# 01-_Power_Regulators.net
KiCad netlist of a schematic drawn in Altium Designer
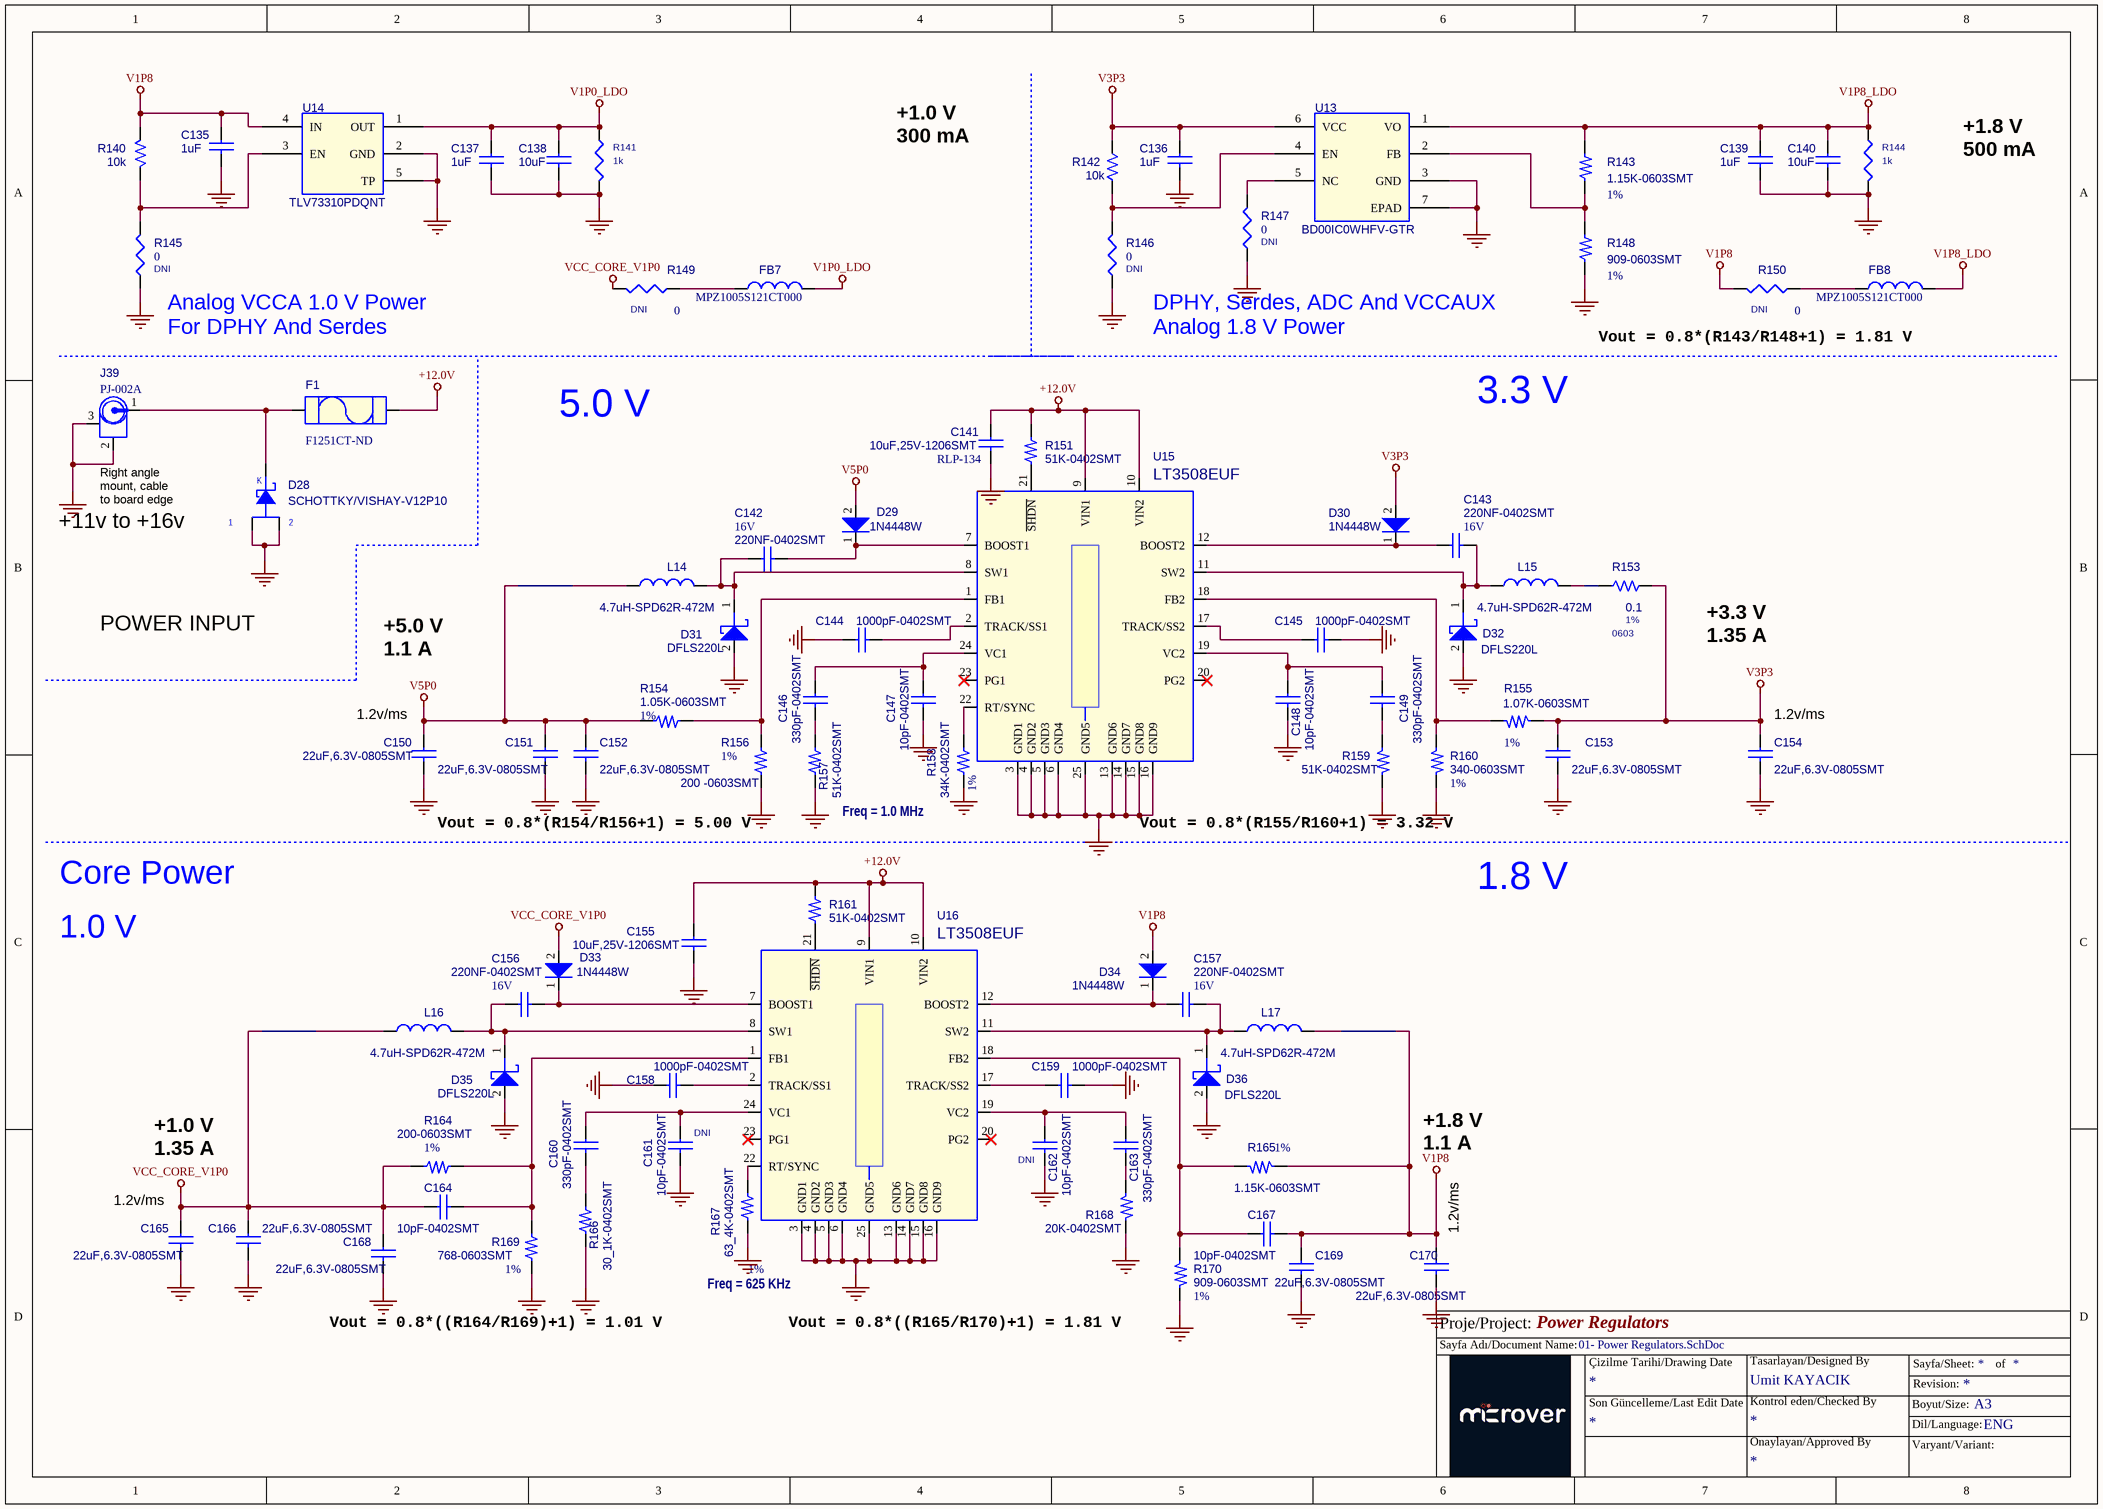
[diagram p0: 01- Power Regulators.SchDoc]

(export (version "E")
  (design (tool "Eeschema 10.0.6"))
  (components
    (comp (ref "C135")
      (value "1uF")
      (footprint "C0603")
      (description "CAP CER 10UF 10V 20% X6S 0603")
      (fields
        (field (name "MANUFACTURER PART NUMBER") "CL10X106MP8NRNC")
        (field (name "MANUFACTURER") "Samsung")
      )
      (libsource (lib "*") (part "CAP NP"))
    )
    (comp (ref "C136")
      (value "1uF")
      (footprint "C0603")
      (description "CAP CER 10UF 10V 20% X6S 0603")
      (fields
        (field (name "MANUFACTURER PART NUMBER") "CL10X106MP8NRNC")
        (field (name "MANUFACTURER") "Samsung")
      )
      (libsource (lib "*") (part "CAP NP"))
    )
    (comp (ref "C137")
      (value "1uF")
      (footprint "C0603")
      (description "CAP CER 10UF 10V 20% X6S 0603")
      (fields
        (field (name "MANUFACTURER PART NUMBER") "CL10X106MP8NRNC")
        (field (name "MANUFACTURER") "Samsung")
      )
      (libsource (lib "*") (part "CAP NP"))
    )
    (comp (ref "C138")
      (value "10uF")
      (footprint "C0603")
      (description "CAP CER 10UF 10V 20% X6S 0603")
      (fields (field (name "MFG") "Samsung") (field (name "MAN. PART #") "CL10X106MP8NRNC"))
      (libsource (lib "*") (part "CAP NP"))
    )
    (comp (ref "C139")
      (value "1uF")
      (footprint "C0603")
      (description "CAP CER 10UF 10V 20% X6S 0603")
      (fields (field (name "MFG") "Samsung") (field (name "MAN. PART #") "CL10X106MP8NRNC"))
      (libsource (lib "*") (part "CAP NP"))
    )
    (comp (ref "C140")
      (value "10uF")
      (footprint "C0603")
      (description "CAP CER 10UF 10V 20% X6S 0603")
      (fields (field (name "MFG") "Samsung") (field (name "MAN. PART #") "CL10X106MP8NRNC"))
      (libsource (lib "*") (part "CAP NP"))
    )
    (comp (ref "C141")
      (value "10uF,25V-1206SMT")
      (footprint "RLP-134")
      (fields (field (name "PCB FOOTPRINT") "RLP-134"))
      (libsource (lib "*") (part "CAP-NP"))
    )
    (comp (ref "C142")
      (value "220NF-0402SMT")
      (footprint "RLP-130-A")
      (fields (field (name "COMPFIXED") "16V"))
      (libsource (lib "*") (part "CAP-NP"))
    )
    (comp (ref "C143")
      (value "220NF-0402SMT")
      (footprint "RLP-130-A")
      (fields (field (name "COMPFIXED") "16V"))
      (libsource (lib "*") (part "CAP-NP"))
    )
    (comp (ref "C144") (value "1000pF-0402SMT") (footprint "RLP-130-A") (libsource (lib "*") (part "CAP-NP")))
    (comp (ref "C145") (value "1000pF-0402SMT") (footprint "RLP-130-A") (libsource (lib "*") (part "CAP-NP")))
    (comp (ref "C146") (value "330pF-0402SMT") (footprint "RLP-130-A") (libsource (lib "*") (part "CAP-NP")))
    (comp (ref "C147") (value "10pF-0402SMT") (footprint "RLP-130-A") (libsource (lib "*") (part "CAP-NP")))
    (comp (ref "C148") (value "10pF-0402SMT") (footprint "RLP-130-A") (libsource (lib "*") (part "CAP-NP")))
    (comp (ref "C149") (value "330pF-0402SMT") (footprint "RLP-130-A") (libsource (lib "*") (part "CAP-NP")))
    (comp (ref "C150")
      (value "22uF,6.3V-0805SMT")
      (footprint "RLP-133")
      (description "CAP CER 22UF 10V X5R 0805")
      (fields
        (field (name "MANUFACTURER") "Samsung")
        (field (name "MANUFACTURER PART NUMBER") "CL21A226KPCLRNC")
      )
      (libsource (lib "*") (part "CAP-NP"))
    )
    (comp (ref "C151")
      (value "22uF,6.3V-0805SMT")
      (footprint "RLP-133")
      (description "CAP CER 22UF 10V X5R 0805")
      (fields
        (field (name "MANUFACTURER") "Samsung")
        (field (name "MANUFACTURER PART NUMBER") "CL21A226KPCLRNC")
      )
      (libsource (lib "*") (part "CAP-NP"))
    )
    (comp (ref "C152")
      (value "22uF,6.3V-0805SMT")
      (footprint "RLP-133")
      (description "CAP CER 22UF 10V X5R 0805")
      (fields
        (field (name "MANUFACTURER") "Samsung")
        (field (name "MANUFACTURER PART NUMBER") "CL21A226KPCLRNC")
      )
      (libsource (lib "*") (part "CAP-NP"))
    )
    (comp (ref "C153")
      (value "22uF,6.3V-0805SMT")
      (footprint "RLP-133")
      (description "CAP CER 22UF 10V X5R 0805")
      (fields
        (field (name "MANUFACTURER PART NUMBER") "CL21A226KPCLRNC")
        (field (name "MANUFACTURER") "Samsung")
      )
      (libsource (lib "*") (part "CAP-NP"))
    )
    (comp (ref "C154")
      (value "22uF,6.3V-0805SMT")
      (footprint "RLP-133")
      (description "CAP CER 22UF 10V X5R 0805")
      (fields
        (field (name "MANUFACTURER PART NUMBER") "CL21A226KPCLRNC")
        (field (name "MANUFACTURER") "Samsung")
      )
      (libsource (lib "*") (part "CAP-NP"))
    )
    (comp (ref "C155") (value "10uF,25V-1206SMT") (footprint "RLP-134") (libsource (lib "*") (part "CAP-NP")))
    (comp (ref "C156")
      (value "220NF-0402SMT")
      (footprint "RLP-130-A")
      (fields (field (name "COMPFIXED") "16V"))
      (libsource (lib "*") (part "CAP-NP"))
    )
    (comp (ref "C157")
      (value "220NF-0402SMT")
      (footprint "RLP-130-A")
      (fields (field (name "COMPFIXED") "16V"))
      (libsource (lib "*") (part "CAP-NP"))
    )
    (comp (ref "C158") (value "1000pF-0402SMT") (footprint "RLP-130-A") (libsource (lib "*") (part "CAP-NP")))
    (comp (ref "C159") (value "1000pF-0402SMT") (footprint "RLP-130-A") (libsource (lib "*") (part "CAP-NP")))
    (comp (ref "C160") (value "330pF-0402SMT") (footprint "RLP-130-A") (libsource (lib "*") (part "CAP-NP")))
    (comp (ref "C161")
      (value "10pF-0402SMT")
      (footprint "RLP-130-A")
      (fields (field (name "POPULATE") "DNI"))
      (libsource (lib "*") (part "CAP-NP"))
    )
    (comp (ref "C162")
      (value "10pF-0402SMT")
      (footprint "RLP-130-A")
      (fields (field (name "POPULATE") "DNI"))
      (libsource (lib "*") (part "CAP-NP"))
    )
    (comp (ref "C163") (value "330pF-0402SMT") (footprint "RLP-130-A") (libsource (lib "*") (part "CAP-NP")))
    (comp (ref "C164") (value "10pF-0402SMT") (footprint "RLP-130-A") (libsource (lib "*") (part "CAP-NP")))
    (comp (ref "C165")
      (value "22uF,6.3V-0805SMT")
      (footprint "RLP-133")
      (description "CAP CER 22UF 10V X5R 0805")
      (fields
        (field (name "MANUFACTURER PART NUMBER") "CL21A226KPCLRNC")
        (field (name "MANUFACTURER") "Samsung")
      )
      (libsource (lib "*") (part "CAP-NP"))
    )
    (comp (ref "C166")
      (value "22uF,6.3V-0805SMT")
      (footprint "RLP-133")
      (description "CAP CER 22UF 10V X5R 0805")
      (fields
        (field (name "MANUFACTURER") "Samsung")
        (field (name "MANUFACTURER PART NUMBER") "CL21A226KPCLRNC")
      )
      (libsource (lib "*") (part "CAP-NP"))
    )
    (comp (ref "C167") (value "10pF-0402SMT") (footprint "RLP-130-A") (libsource (lib "*") (part "CAP-NP")))
    (comp (ref "C168")
      (value "22uF,6.3V-0805SMT")
      (footprint "RLP-133")
      (description "CAP CER 22UF 10V X5R 0805")
      (fields
        (field (name "MANUFACTURER") "Samsung")
        (field (name "MANUFACTURER PART NUMBER") "CL21A226KPCLRNC")
      )
      (libsource (lib "*") (part "CAP-NP"))
    )
    (comp (ref "C169")
      (value "22uF,6.3V-0805SMT")
      (footprint "RLP-133")
      (description "CAP CER 22UF 10V X5R 0805")
      (fields
        (field (name "MANUFACTURER PART NUMBER") "CL21A226KPCLRNC")
        (field (name "MANUFACTURER") "Samsung")
      )
      (libsource (lib "*") (part "CAP-NP"))
    )
    (comp (ref "C170")
      (value "22uF,6.3V-0805SMT")
      (footprint "RLP-133")
      (description "CAP CER 22UF 10V X5R 0805")
      (fields
        (field (name "MANUFACTURER") "Samsung")
        (field (name "MANUFACTURER PART NUMBER") "CL21A226KPCLRNC")
      )
      (libsource (lib "*") (part "CAP-NP"))
    )
    (comp (ref "D28")
      (value "SCHOTTKY/VISHAY-V12P10")
      (footprint "V12P10")
      (libsource (lib "*") (part "DIODE SCHOTTKY21"))
    )
    (comp (ref "D29") (value "1N4448W") (footprint "1N4448W") (libsource (lib "*") (part "DIODE_0")))
    (comp (ref "D30") (value "1N4448W") (footprint "1N4448W") (libsource (lib "*") (part "DIODE_0")))
    (comp (ref "D31") (value "DFLS220L") (footprint "DFLS220L") (libsource (lib "*") (part "D-SCHOTTKY_0")))
    (comp (ref "D32") (value "DFLS220L") (footprint "DFLS220L") (libsource (lib "*") (part "D-SCHOTTKY_0")))
    (comp (ref "D33") (value "1N4448W") (footprint "1N4448W") (libsource (lib "*") (part "DIODE_0")))
    (comp (ref "D34") (value "1N4448W") (footprint "1N4448W") (libsource (lib "*") (part "DIODE_0")))
    (comp (ref "D35") (value "DFLS220L") (footprint "DFLS220L") (libsource (lib "*") (part "D-SCHOTTKY_0")))
    (comp (ref "D36") (value "DFLS220L") (footprint "DFLS220L") (libsource (lib "*") (part "D-SCHOTTKY_0")))
    (comp (ref "F1")
      (value "F1251CT-ND")
      (footprint "0154010")
      (description "5A Fast-Blo SMT Socketed Fuse")
      (libsource (lib "*") (part "SMTFUSE_0"))
    )
    (comp (ref "FB7")
      (value "MPZ1005S121CT000")
      (footprint "FB0402")
      (description "FERRITE BEAD 120 OHM 0402 1LN")
      (fields (field (name "MANUFACTURER") "TDK Corporation"))
      (libsource (lib "*") (part "INDUCTOR_1"))
    )
    (comp (ref "FB8")
      (value "MPZ1005S121CT000")
      (footprint "FB0402")
      (description "FERRITE BEAD 120 OHM 0402 1LN")
      (fields (field (name "MANUFACTURER") "TDK Corporation"))
      (libsource (lib "*") (part "INDUCTOR_1"))
    )
    (comp (ref "J39")
      (value "PJ-002A")
      (footprint "pj_002a_3p")
      (description "Male Power Jack 2.1mm")
      (libsource (lib "*") (part "22HP037A"))
    )
    (comp (ref "L14") (value "4.7uH-SPD62R-472M") (footprint "SPD62R") (libsource (lib "*") (part "IND")))
    (comp (ref "L15") (value "4.7uH-SPD62R-472M") (footprint "SPD62R") (libsource (lib "") (part "IND_1")))
    (comp (ref "L16") (value "4.7uH-SPD62R-472M") (footprint "SPD62R") (libsource (lib "*") (part "IND")))
    (comp (ref "L17") (value "4.7uH-SPD62R-472M") (footprint "SPD62R") (libsource (lib "") (part "IND_1")))
    (comp (ref "R140")
      (value "10k")
      (footprint "R0402")
      (description "RES SMD 4.7K OHM 5% 1/10W 0402")
      (fields (field (name "VOLTAGE") "RVMAX") (field (name "POWER") "RMAX"))
      (libsource (lib "Chronos") (part "R_Dup2"))
    )
    (comp (ref "R141")
      (value "1k")
      (footprint "R0402")
      (description "RES SMD 1K OHM 1% 1/10W 0402")
      (fields
        (field (name "MFG") "Stackpole Electronics Inc")
        (field (name "MANUFACTURER PART NUMBER") "ERJ-2RKF1001X")
      )
      (libsource (lib "*") (part "RES_1K_1W16_0402_5P"))
    )
    (comp (ref "R142")
      (value "10k")
      (footprint "R0402")
      (description "RES SMD 4.7K OHM 5% 1/10W 0402")
      (fields (field (name "VOLTAGE") "RVMAX") (field (name "POWER") "RMAX"))
      (libsource (lib "*") (part "R_Dup2"))
    )
    (comp (ref "R143")
      (value "1.15K-0603SMT")
      (footprint "RLP-101")
      (fields (field (name "COMPFIXED") "1%"))
      (libsource (lib "*") (part "R_Dup1"))
    )
    (comp (ref "R144")
      (value "1k")
      (footprint "R0402")
      (description "RES SMD 1K OHM 1% 1/10W 0402")
      (fields
        (field (name "MFG") "Stackpole Electronics Inc")
        (field (name "MANUFACTURER PART NUMBER") "ERJ-2RKF1001X")
      )
      (libsource (lib "*") (part "RES_1K_1W16_0402_5P"))
    )
    (comp (ref "R145")
      (value "0")
      (footprint "R0402")
      (description "RES 0.0 OHM 1/10W JUMP 0402 SMD")
      (fields
        (field (name "MANUFACTURER") "Yageo")
        (field (name "MANUFACTURER PART NUMBER") "RC0603JR-070RL")
        (field (name "ASSY") "DNI")
      )
      (libsource (lib "*") (part "0R_0603"))
    )
    (comp (ref "R146")
      (value "0")
      (footprint "R0603")
      (description "RES 0.0 OHM 1/10W JUMP 0603 SMD")
      (fields
        (field (name "MANUFACTURER") "Yageo")
        (field (name "MANUFACTURER PART NUMBER") "RC0603JR-070RL")
        (field (name "ASSY") "DNI")
      )
      (libsource (lib "*") (part "0R_0603"))
    )
    (comp (ref "R147")
      (value "0")
      (footprint "R0603")
      (description "RES 0.0 OHM 1/10W JUMP 0603 SMD")
      (fields
        (field (name "MANUFACTURER") "Yageo")
        (field (name "MANUFACTURER PART NUMBER") "RC0603JR-070RL")
        (field (name "ASSY") "DNI")
      )
      (libsource (lib "*") (part "0R_0603"))
    )
    (comp (ref "R148")
      (value "909-0603SMT")
      (footprint "RLP-101")
      (fields (field (name "COMPFIXED") "1%"))
      (libsource (lib "*") (part "R_Dup1"))
    )
    (comp (ref "R149")
      (value "0")
      (footprint "R0603")
      (description "RES 0.0 OHM 1/10W JUMP 0603 SMD")
      (fields
        (field (name "MANUFACTURER") "Yageo")
        (field (name "MANUFACTURER PART NUMBER") "RC0603JR-070RL")
        (field (name "ASSY") "DNI")
      )
      (libsource (lib "*") (part "0R_0603"))
    )
    (comp (ref "R150")
      (value "0")
      (footprint "R0603")
      (description "RES 0.0 OHM 1/10W JUMP 0603 SMD")
      (fields
        (field (name "MANUFACTURER") "Yageo")
        (field (name "MANUFACTURER PART NUMBER") "RC0603JR-070RL")
        (field (name "ASSY") "DNI")
      )
      (libsource (lib "*") (part "0R_0603"))
    )
    (comp (ref "R151") (value "51K-0402SMT") (footprint "RLP-100") (libsource (lib "*") (part "R_Dup1")))
    (comp (ref "R153")
      (value "0.1")
      (footprint "0603")
      (fields
        (field (name "VOLTAGE") "RVMAX")
        (field (name "POWER") "RMAX")
        (field (name "TOLLERANCE") "1%")
        (field (name "PCB FOOTPRINT") "0603")
      )
      (libsource (lib "*") (part "R_Dup2"))
    )
    (comp (ref "R154")
      (value "1.05K-0603SMT")
      (footprint "RLP-101")
      (fields (field (name "COMPFIXED") "1%"))
      (libsource (lib "*") (part "R_Dup1"))
    )
    (comp (ref "R155")
      (value "1.07K-0603SMT")
      (footprint "RLP-101")
      (fields (field (name "COMPFIXED") "1%"))
      (libsource (lib "*") (part "R_Dup1"))
    )
    (comp (ref "R156")
      (value "200 -0603SMT")
      (footprint "RLP-101")
      (fields (field (name "COMPFIXED") "1%"))
      (libsource (lib "*") (part "R_Dup1"))
    )
    (comp (ref "R157") (value "51K-0402SMT") (footprint "RLP-100") (libsource (lib "*") (part "R_Dup1")))
    (comp (ref "R158")
      (value "34K-0402SMT")
      (footprint "RLP-100")
      (fields (field (name "COMPGROUP") "Freq = 1.0 MHz") (field (name "COMPFIXED") "1%"))
      (libsource (lib "*") (part "R_Dup1"))
    )
    (comp (ref "R159") (value "51K-0402SMT") (footprint "RLP-100") (libsource (lib "*") (part "R_Dup1")))
    (comp (ref "R160")
      (value "340-0603SMT")
      (footprint "RLP-101")
      (fields (field (name "COMPFIXED") "1%"))
      (libsource (lib "*") (part "R_Dup1"))
    )
    (comp (ref "R161") (value "51K-0402SMT") (footprint "RLP-100") (libsource (lib "*") (part "R_Dup1")))
    (comp (ref "R164")
      (value "200-0603SMT")
      (footprint "RLP-101")
      (fields (field (name "COMPFIXED") "1%"))
      (libsource (lib "*") (part "R_Dup1"))
    )
    (comp (ref "R165")
      (value "1.15K-0603SMT")
      (footprint "RLP-101")
      (fields (field (name "COMPFIXED") "1%"))
      (libsource (lib "*") (part "R_Dup1"))
    )
    (comp (ref "R166") (value "30_1K-0402SMT") (footprint "RLP-100") (libsource (lib "*") (part "R_Dup1")))
    (comp (ref "R167")
      (value "63_4K-0402SMT")
      (footprint "RLP-100")
      (fields (field (name "COMPGROUP") "Freq = 625 KHz") (field (name "COMPFIXED") "1%"))
      (libsource (lib "*") (part "R_Dup1"))
    )
    (comp (ref "R168") (value "20K-0402SMT") (footprint "RLP-100") (libsource (lib "*") (part "R_Dup1")))
    (comp (ref "R169")
      (value "768-0603SMT")
      (footprint "RLP-101")
      (fields (field (name "COMPFIXED") "1%"))
      (libsource (lib "*") (part "R_Dup1"))
    )
    (comp (ref "R170")
      (value "909-0603SMT")
      (footprint "RLP-101")
      (fields (field (name "COMPFIXED") "1%"))
      (libsource (lib "*") (part "R_Dup1"))
    )
    (comp (ref "U13")
      (value "BD00IC0WHFV-GTR")
      (footprint "6HVSOF_BD00IC0WHFV")
      (libsource (lib "*") (part "BD00IC0WHFV-GTR"))
    )
    (comp (ref "U14")
      (value "TLV73310PDQNT")
      (footprint "4X2SON")
      (libsource (lib "*") (part "TLV73310PDQNT"))
    )
    (comp (ref "U15")
      (value "LT3508EUF")
      (footprint "LT3508EUF")
      (libsource (lib "*") (part "LT3508EUF-QFN24UF-4X4_0"))
    )
    (comp (ref "U16")
      (value "LT3508EUF")
      (footprint "LT3508EUF")
      (libsource (lib "*") (part "LT3508EUF-QFN24UF-4X4_0"))
    )
  )
  (nets
    (net (code "1") (name "+12.0V") (class "Default")
      (node (ref "C141") (pin "1") (pinfunction "1_1") (pintype "passive"))
      (node (ref "C155") (pin "1") (pinfunction "1_1") (pintype "passive"))
      (node (ref "F1") (pin "2") (pinfunction "2_2") (pintype "passive"))
      (node (ref "R151") (pin "1") (pinfunction "1_1") (pintype "passive"))
      (node (ref "R161") (pin "1") (pinfunction "1_1") (pintype "passive"))
      (node (ref "U15") (pin "10") (pinfunction "VIN2_10") (pintype "passive"))
      (node (ref "U15") (pin "9") (pinfunction "VIN1_9") (pintype "passive"))
      (node (ref "U16") (pin "10") (pinfunction "VIN2_10") (pintype "passive"))
      (node (ref "U16") (pin "9") (pinfunction "VIN1_9") (pintype "passive"))
    )
    (net (code "2") (name "GND") (class "Default")
      (node (ref "C135") (pin "2") (pinfunction "2_2") (pintype "passive"))
      (node (ref "C136") (pin "2") (pinfunction "2_2") (pintype "passive"))
      (node (ref "C137") (pin "2") (pinfunction "2_2") (pintype "passive"))
      (node (ref "C138") (pin "2") (pinfunction "2_2") (pintype "passive"))
      (node (ref "C139") (pin "2") (pinfunction "2_2") (pintype "passive"))
      (node (ref "C140") (pin "2") (pinfunction "2_2") (pintype "passive"))
      (node (ref "C141") (pin "2") (pinfunction "2_2") (pintype "passive"))
      (node (ref "C144") (pin "1") (pinfunction "1_1") (pintype "passive"))
      (node (ref "C145") (pin "2") (pinfunction "2_2") (pintype "passive"))
      (node (ref "C147") (pin "2") (pinfunction "2_2") (pintype "passive"))
      (node (ref "C148") (pin "2") (pinfunction "2_2") (pintype "passive"))
      (node (ref "C150") (pin "2") (pinfunction "2_2") (pintype "passive"))
      (node (ref "C151") (pin "2") (pinfunction "2_2") (pintype "passive"))
      (node (ref "C152") (pin "2") (pinfunction "2_2") (pintype "passive"))
      (node (ref "C153") (pin "2") (pinfunction "2_2") (pintype "passive"))
      (node (ref "C154") (pin "2") (pinfunction "2_2") (pintype "passive"))
      (node (ref "C155") (pin "2") (pinfunction "2_2") (pintype "passive"))
      (node (ref "C158") (pin "1") (pinfunction "1_1") (pintype "passive"))
      (node (ref "C159") (pin "2") (pinfunction "2_2") (pintype "passive"))
      (node (ref "C161") (pin "2") (pinfunction "2_2") (pintype "passive"))
      (node (ref "C162") (pin "2") (pinfunction "2_2") (pintype "passive"))
      (node (ref "C165") (pin "2") (pinfunction "2_2") (pintype "passive"))
      (node (ref "C166") (pin "2") (pinfunction "2_2") (pintype "passive"))
      (node (ref "C168") (pin "2") (pinfunction "2_2") (pintype "passive"))
      (node (ref "C169") (pin "2") (pinfunction "2_2") (pintype "passive"))
      (node (ref "C170") (pin "2") (pinfunction "2_2") (pintype "passive"))
      (node (ref "D28") (pin "1") (pinfunction "Anode1_1") (pintype "passive"))
      (node (ref "D28") (pin "2") (pinfunction "Anode2_2") (pintype "passive"))
      (node (ref "D31") (pin "2") (pinfunction "2_2") (pintype "passive"))
      (node (ref "D32") (pin "2") (pinfunction "2_2") (pintype "passive"))
      (node (ref "D35") (pin "2") (pinfunction "2_2") (pintype "passive"))
      (node (ref "D36") (pin "2") (pinfunction "2_2") (pintype "passive"))
      (node (ref "J39") (pin "2") (pinfunction "GND_2") (pintype "power_in"))
      (node (ref "J39") (pin "3") (pinfunction "GND_3") (pintype "power_in"))
      (node (ref "R141") (pin "2") (pinfunction "2_2") (pintype "passive"))
      (node (ref "R144") (pin "2") (pinfunction "2_2") (pintype "passive"))
      (node (ref "R145") (pin "2") (pinfunction "2_2") (pintype "passive"))
      (node (ref "R146") (pin "2") (pinfunction "2_2") (pintype "passive"))
      (node (ref "R147") (pin "2") (pinfunction "2_2") (pintype "passive"))
      (node (ref "R148") (pin "1") (pinfunction "1_1") (pintype "passive"))
      (node (ref "R156") (pin "2") (pinfunction "2_2") (pintype "passive"))
      (node (ref "R157") (pin "2") (pinfunction "2_2") (pintype "passive"))
      (node (ref "R158") (pin "2") (pinfunction "2_2") (pintype "passive"))
      (node (ref "R159") (pin "2") (pinfunction "2_2") (pintype "passive"))
      (node (ref "R160") (pin "2") (pinfunction "2_2") (pintype "passive"))
      (node (ref "R166") (pin "2") (pinfunction "2_2") (pintype "passive"))
      (node (ref "R167") (pin "2") (pinfunction "2_2") (pintype "passive"))
      (node (ref "R168") (pin "2") (pinfunction "2_2") (pintype "passive"))
      (node (ref "R169") (pin "2") (pinfunction "2_2") (pintype "passive"))
      (node (ref "R170") (pin "2") (pinfunction "2_2") (pintype "passive"))
      (node (ref "U13") (pin "3") (pinfunction "GND_3") (pintype "power_in"))
      (node (ref "U13") (pin "7") (pinfunction "EPAD_7") (pintype "power_in"))
      (node (ref "U14") (pin "2") (pinfunction "GND_2") (pintype "passive"))
      (node (ref "U14") (pin "5") (pinfunction "TP_5") (pintype "passive"))
      (node (ref "U15") (pin "13") (pinfunction "GND6_13") (pintype "passive"))
      (node (ref "U15") (pin "14") (pinfunction "GND7_14") (pintype "passive"))
      (node (ref "U15") (pin "15") (pinfunction "GND8_15") (pintype "passive"))
      (node (ref "U15") (pin "16") (pinfunction "GND9_16") (pintype "passive"))
      (node (ref "U15") (pin "25") (pinfunction "GND5_25") (pintype "passive"))
      (node (ref "U15") (pin "3") (pinfunction "GND1_3") (pintype "passive"))
      (node (ref "U15") (pin "4") (pinfunction "GND2_4") (pintype "passive"))
      (node (ref "U15") (pin "5") (pinfunction "GND3_5") (pintype "passive"))
      (node (ref "U15") (pin "6") (pinfunction "GND4_6") (pintype "passive"))
      (node (ref "U16") (pin "13") (pinfunction "GND6_13") (pintype "passive"))
      (node (ref "U16") (pin "14") (pinfunction "GND7_14") (pintype "passive"))
      (node (ref "U16") (pin "15") (pinfunction "GND8_15") (pintype "passive"))
      (node (ref "U16") (pin "16") (pinfunction "GND9_16") (pintype "passive"))
      (node (ref "U16") (pin "25") (pinfunction "GND5_25") (pintype "passive"))
      (node (ref "U16") (pin "3") (pinfunction "GND1_3") (pintype "passive"))
      (node (ref "U16") (pin "4") (pinfunction "GND2_4") (pintype "passive"))
      (node (ref "U16") (pin "5") (pinfunction "GND3_5") (pintype "passive"))
      (node (ref "U16") (pin "6") (pinfunction "GND4_6") (pintype "passive"))
    )
    (net (code "3") (name "Net-(C146-Pad2)") (class "Default")
      (node (ref "C146") (pin "2") (pinfunction "2_2") (pintype "passive"))
      (node (ref "R157") (pin "1") (pinfunction "1_1") (pintype "passive"))
    )
    (net (code "4") (name "Net-(C149-Pad2)") (class "Default")
      (node (ref "C149") (pin "2") (pinfunction "2_2") (pintype "passive"))
      (node (ref "R159") (pin "1") (pinfunction "1_1") (pintype "passive"))
    )
    (net (code "5") (name "Net-(C160-Pad2)") (class "Default")
      (node (ref "C160") (pin "2") (pinfunction "2_2") (pintype "passive"))
      (node (ref "R166") (pin "1") (pinfunction "1_1") (pintype "passive"))
    )
    (net (code "6") (name "Net-(C163-Pad2)") (class "Default")
      (node (ref "C163") (pin "2") (pinfunction "2_2") (pintype "passive"))
      (node (ref "R168") (pin "1") (pinfunction "1_1") (pintype "passive"))
    )
    (net (code "7") (name "Net-(D28-K)") (class "Default")
      (node (ref "D28") (pin "3") (pinfunction "K_3") (pintype "passive"))
      (node (ref "F1") (pin "1") (pinfunction "1_1") (pintype "passive"))
      (node (ref "J39") (pin "1") (pinfunction "+5V_1") (pintype "passive"))
    )
    (net (code "8") (name "Net-(FB7-Pad1)") (class "Default")
      (node (ref "FB7") (pin "1") (pinfunction "1_1") (pintype "passive"))
      (node (ref "R149") (pin "1") (pinfunction "1_1") (pintype "passive"))
    )
    (net (code "9") (name "Net-(FB8-Pad1)") (class "Default")
      (node (ref "FB8") (pin "1") (pinfunction "1_1") (pintype "passive"))
      (node (ref "R150") (pin "1") (pinfunction "1_1") (pintype "passive"))
    )
    (net (code "10") (name "Net-(L15-Pad1)") (class "Default")
      (node (ref "L15") (pin "1") (pinfunction "1_1") (pintype "passive"))
      (node (ref "R153") (pin "1") (pinfunction "1_1") (pintype "passive"))
    )
    (net (code "11") (name "Net-(U13-EN)") (class "Default")
      (node (ref "R142") (pin "1") (pinfunction "1_1") (pintype "passive"))
      (node (ref "R146") (pin "1") (pinfunction "1_1") (pintype "passive"))
      (node (ref "U13") (pin "4") (pinfunction "EN_4") (pintype "power_in"))
    )
    (net (code "12") (name "Net-(U13-FB)") (class "Default")
      (node (ref "R143") (pin "1") (pinfunction "1_1") (pintype "passive"))
      (node (ref "R148") (pin "2") (pinfunction "2_2") (pintype "passive"))
      (node (ref "U13") (pin "2") (pinfunction "FB_2") (pintype "power_in"))
    )
    (net (code "13") (name "Net-(U13-NC)") (class "Default")
      (node (ref "R147") (pin "1") (pinfunction "1_1") (pintype "passive"))
      (node (ref "U13") (pin "5") (pinfunction "NC_5") (pintype "power_in"))
    )
    (net (code "14") (name "Net-(U14-EN)") (class "Default")
      (node (ref "R140") (pin "1") (pinfunction "1_1") (pintype "passive"))
      (node (ref "R145") (pin "1") (pinfunction "1_1") (pintype "passive"))
      (node (ref "U14") (pin "3") (pinfunction "EN_3") (pintype "passive"))
    )
    (net (code "15") (name "Net-(U15-BOOST1)") (class "Default")
      (node (ref "C142") (pin "2") (pinfunction "2_2") (pintype "passive"))
      (node (ref "D29") (pin "1") (pinfunction "1_1") (pintype "passive"))
      (node (ref "U15") (pin "7") (pinfunction "BOOST1_7") (pintype "passive"))
    )
    (net (code "16") (name "Net-(U15-BOOST2)") (class "Default")
      (node (ref "C143") (pin "1") (pinfunction "1_1") (pintype "passive"))
      (node (ref "D30") (pin "1") (pinfunction "1_1") (pintype "passive"))
      (node (ref "U15") (pin "12") (pinfunction "BOOST2_12") (pintype "passive"))
    )
    (net (code "17") (name "Net-(U15-FB1)") (class "Default")
      (node (ref "R154") (pin "2") (pinfunction "2_2") (pintype "passive"))
      (node (ref "R156") (pin "1") (pinfunction "1_1") (pintype "passive"))
      (node (ref "U15") (pin "1") (pinfunction "FB1_1") (pintype "passive"))
    )
    (net (code "18") (name "Net-(U15-FB2)") (class "Default")
      (node (ref "R155") (pin "2") (pinfunction "2_2") (pintype "passive"))
      (node (ref "R160") (pin "1") (pinfunction "1_1") (pintype "passive"))
      (node (ref "U15") (pin "18") (pinfunction "FB2_18") (pintype "passive"))
    )
    (net (code "19") (name "Net-(U15-RT{slash}SYNC)") (class "Default")
      (node (ref "R158") (pin "1") (pinfunction "1_1") (pintype "passive"))
      (node (ref "U15") (pin "22") (pinfunction "RT/SYNC_22") (pintype "passive"))
    )
    (net (code "20") (name "Net-(U15-SW1)") (class "Default")
      (node (ref "C142") (pin "1") (pinfunction "1_1") (pintype "passive"))
      (node (ref "D31") (pin "1") (pinfunction "1_1") (pintype "passive"))
      (node (ref "L14") (pin "2") (pinfunction "2_2") (pintype "passive"))
      (node (ref "U15") (pin "8") (pinfunction "SW1_8") (pintype "passive"))
    )
    (net (code "21") (name "Net-(U15-SW2)") (class "Default")
      (node (ref "C143") (pin "2") (pinfunction "2_2") (pintype "passive"))
      (node (ref "D32") (pin "1") (pinfunction "1_1") (pintype "passive"))
      (node (ref "L15") (pin "2") (pinfunction "2_2") (pintype "passive"))
      (node (ref "U15") (pin "11") (pinfunction "SW2_11") (pintype "passive"))
    )
    (net (code "22") (name "Net-(U15-TRACK{slash}SS1)") (class "Default")
      (node (ref "C144") (pin "2") (pinfunction "2_2") (pintype "passive"))
      (node (ref "U15") (pin "2") (pinfunction "TRACK/SS1_2") (pintype "passive"))
    )
    (net (code "23") (name "Net-(U15-TRACK{slash}SS2)") (class "Default")
      (node (ref "C145") (pin "1") (pinfunction "1_1") (pintype "passive"))
      (node (ref "U15") (pin "17") (pinfunction "TRACK/SS2_17") (pintype "passive"))
    )
    (net (code "24") (name "Net-(U15-VC1)") (class "Default")
      (node (ref "C146") (pin "1") (pinfunction "1_1") (pintype "passive"))
      (node (ref "C147") (pin "1") (pinfunction "1_1") (pintype "passive"))
      (node (ref "U15") (pin "24") (pinfunction "VC1_24") (pintype "passive"))
    )
    (net (code "25") (name "Net-(U15-VC2)") (class "Default")
      (node (ref "C148") (pin "1") (pinfunction "1_1") (pintype "passive"))
      (node (ref "C149") (pin "1") (pinfunction "1_1") (pintype "passive"))
      (node (ref "U15") (pin "19") (pinfunction "VC2_19") (pintype "passive"))
    )
    (net (code "26") (name "Net-(U15-~{SHDN})") (class "Default")
      (node (ref "R151") (pin "2") (pinfunction "2_2") (pintype "passive"))
      (node (ref "U15") (pin "21") (pinfunction "~{SHDN}_21") (pintype "passive"))
    )
    (net (code "27") (name "Net-(U16-BOOST1)") (class "Default")
      (node (ref "C156") (pin "2") (pinfunction "2_2") (pintype "passive"))
      (node (ref "D33") (pin "1") (pinfunction "1_1") (pintype "passive"))
      (node (ref "U16") (pin "7") (pinfunction "BOOST1_7") (pintype "passive"))
    )
    (net (code "28") (name "Net-(U16-BOOST2)") (class "Default")
      (node (ref "C157") (pin "1") (pinfunction "1_1") (pintype "passive"))
      (node (ref "D34") (pin "1") (pinfunction "1_1") (pintype "passive"))
      (node (ref "U16") (pin "12") (pinfunction "BOOST2_12") (pintype "passive"))
    )
    (net (code "29") (name "Net-(U16-FB1)") (class "Default")
      (node (ref "C164") (pin "2") (pinfunction "2_2") (pintype "passive"))
      (node (ref "R164") (pin "2") (pinfunction "2_2") (pintype "passive"))
      (node (ref "R169") (pin "1") (pinfunction "1_1") (pintype "passive"))
      (node (ref "U16") (pin "1") (pinfunction "FB1_1") (pintype "passive"))
    )
    (net (code "30") (name "Net-(U16-FB2)") (class "Default")
      (node (ref "C167") (pin "1") (pinfunction "1_1") (pintype "passive"))
      (node (ref "R165") (pin "2") (pinfunction "2_2") (pintype "passive"))
      (node (ref "R170") (pin "1") (pinfunction "1_1") (pintype "passive"))
      (node (ref "U16") (pin "18") (pinfunction "FB2_18") (pintype "passive"))
    )
    (net (code "31") (name "Net-(U16-RT{slash}SYNC)") (class "Default")
      (node (ref "R167") (pin "1") (pinfunction "1_1") (pintype "passive"))
      (node (ref "U16") (pin "22") (pinfunction "RT/SYNC_22") (pintype "passive"))
    )
    (net (code "32") (name "Net-(U16-SW1)") (class "Default")
      (node (ref "C156") (pin "1") (pinfunction "1_1") (pintype "passive"))
      (node (ref "D35") (pin "1") (pinfunction "1_1") (pintype "passive"))
      (node (ref "L16") (pin "2") (pinfunction "2_2") (pintype "passive"))
      (node (ref "U16") (pin "8") (pinfunction "SW1_8") (pintype "passive"))
    )
    (net (code "33") (name "Net-(U16-SW2)") (class "Default")
      (node (ref "C157") (pin "2") (pinfunction "2_2") (pintype "passive"))
      (node (ref "D36") (pin "1") (pinfunction "1_1") (pintype "passive"))
      (node (ref "L17") (pin "2") (pinfunction "2_2") (pintype "passive"))
      (node (ref "U16") (pin "11") (pinfunction "SW2_11") (pintype "passive"))
    )
    (net (code "34") (name "Net-(U16-TRACK{slash}SS1)") (class "Default")
      (node (ref "C158") (pin "2") (pinfunction "2_2") (pintype "passive"))
      (node (ref "U16") (pin "2") (pinfunction "TRACK/SS1_2") (pintype "passive"))
    )
    (net (code "35") (name "Net-(U16-TRACK{slash}SS2)") (class "Default")
      (node (ref "C159") (pin "1") (pinfunction "1_1") (pintype "passive"))
      (node (ref "U16") (pin "17") (pinfunction "TRACK/SS2_17") (pintype "passive"))
    )
    (net (code "36") (name "Net-(U16-VC1)") (class "Default")
      (node (ref "C160") (pin "1") (pinfunction "1_1") (pintype "passive"))
      (node (ref "C161") (pin "1") (pinfunction "1_1") (pintype "passive"))
      (node (ref "U16") (pin "24") (pinfunction "VC1_24") (pintype "passive"))
    )
    (net (code "37") (name "Net-(U16-VC2)") (class "Default")
      (node (ref "C162") (pin "1") (pinfunction "1_1") (pintype "passive"))
      (node (ref "C163") (pin "1") (pinfunction "1_1") (pintype "passive"))
      (node (ref "U16") (pin "19") (pinfunction "VC2_19") (pintype "passive"))
    )
    (net (code "38") (name "Net-(U16-~{SHDN})") (class "Default")
      (node (ref "R161") (pin "2") (pinfunction "2_2") (pintype "passive"))
      (node (ref "U16") (pin "21") (pinfunction "~{SHDN}_21") (pintype "passive"))
    )
    (net (code "39") (name "V1P0_LDO") (class "Default")
      (node (ref "C137") (pin "1") (pinfunction "1_1") (pintype "passive"))
      (node (ref "C138") (pin "1") (pinfunction "1_1") (pintype "passive"))
      (node (ref "FB7") (pin "2") (pinfunction "2_2") (pintype "passive"))
      (node (ref "R141") (pin "1") (pinfunction "1_1") (pintype "passive"))
      (node (ref "U14") (pin "1") (pinfunction "OUT_1") (pintype "passive"))
    )
    (net (code "40") (name "V1P8") (class "Default")
      (node (ref "C135") (pin "1") (pinfunction "1_1") (pintype "passive"))
      (node (ref "C167") (pin "2") (pinfunction "2_2") (pintype "passive"))
      (node (ref "C169") (pin "1") (pinfunction "1_1") (pintype "passive"))
      (node (ref "C170") (pin "1") (pinfunction "1_1") (pintype "passive"))
      (node (ref "D34") (pin "2") (pinfunction "2_2") (pintype "passive"))
      (node (ref "L17") (pin "1") (pinfunction "1_1") (pintype "passive"))
      (node (ref "R140") (pin "2") (pinfunction "2_2") (pintype "passive"))
      (node (ref "R150") (pin "2") (pinfunction "2_2") (pintype "passive"))
      (node (ref "R165") (pin "1") (pinfunction "1_1") (pintype "passive"))
      (node (ref "U14") (pin "4") (pinfunction "IN_4") (pintype "passive"))
    )
    (net (code "41") (name "V1P8_LDO") (class "Default")
      (node (ref "C139") (pin "1") (pinfunction "1_1") (pintype "passive"))
      (node (ref "C140") (pin "1") (pinfunction "1_1") (pintype "passive"))
      (node (ref "FB8") (pin "2") (pinfunction "2_2") (pintype "passive"))
      (node (ref "R143") (pin "2") (pinfunction "2_2") (pintype "passive"))
      (node (ref "R144") (pin "1") (pinfunction "1_1") (pintype "passive"))
      (node (ref "U13") (pin "1") (pinfunction "VO_1") (pintype "power_in"))
    )
    (net (code "42") (name "V3P3") (class "Default")
      (node (ref "C136") (pin "1") (pinfunction "1_1") (pintype "passive"))
      (node (ref "C153") (pin "1") (pinfunction "1_1") (pintype "passive"))
      (node (ref "C154") (pin "1") (pinfunction "1_1") (pintype "passive"))
      (node (ref "D30") (pin "2") (pinfunction "2_2") (pintype "passive"))
      (node (ref "R142") (pin "2") (pinfunction "2_2") (pintype "passive"))
      (node (ref "R153") (pin "2") (pinfunction "2_2") (pintype "passive"))
      (node (ref "R155") (pin "1") (pinfunction "1_1") (pintype "passive"))
      (node (ref "U13") (pin "6") (pinfunction "VCC_6") (pintype "power_in"))
    )
    (net (code "43") (name "V5P0") (class "Default")
      (node (ref "C150") (pin "1") (pinfunction "1_1") (pintype "passive"))
      (node (ref "C151") (pin "1") (pinfunction "1_1") (pintype "passive"))
      (node (ref "C152") (pin "1") (pinfunction "1_1") (pintype "passive"))
      (node (ref "D29") (pin "2") (pinfunction "2_2") (pintype "passive"))
      (node (ref "L14") (pin "1") (pinfunction "1_1") (pintype "passive"))
      (node (ref "R154") (pin "1") (pinfunction "1_1") (pintype "passive"))
    )
    (net (code "44") (name "VCC_CORE_V1P0") (class "Default")
      (node (ref "C164") (pin "1") (pinfunction "1_1") (pintype "passive"))
      (node (ref "C165") (pin "1") (pinfunction "1_1") (pintype "passive"))
      (node (ref "C166") (pin "1") (pinfunction "1_1") (pintype "passive"))
      (node (ref "C168") (pin "1") (pinfunction "1_1") (pintype "passive"))
      (node (ref "D33") (pin "2") (pinfunction "2_2") (pintype "passive"))
      (node (ref "L16") (pin "1") (pinfunction "1_1") (pintype "passive"))
      (node (ref "R149") (pin "2") (pinfunction "2_2") (pintype "passive"))
      (node (ref "R164") (pin "1") (pinfunction "1_1") (pintype "passive"))
    )
    (net (code "45") (name "unconnected-(U15-PG1-Pad23)") (class "Default")
      (node (ref "U15") (pin "23") (pinfunction "PG1_23") (pintype "passive+no_connect"))
    )
    (net (code "46") (name "unconnected-(U15-PG2-Pad20)") (class "Default")
      (node (ref "U15") (pin "20") (pinfunction "PG2_20") (pintype "passive+no_connect"))
    )
    (net (code "47") (name "unconnected-(U16-PG1-Pad23)") (class "Default")
      (node (ref "U16") (pin "23") (pinfunction "PG1_23") (pintype "passive+no_connect"))
    )
    (net (code "48") (name "unconnected-(U16-PG2-Pad20)") (class "Default")
      (node (ref "U16") (pin "20") (pinfunction "PG2_20") (pintype "passive+no_connect"))
    )
  )
)
